# Adafruit_VCNL4200_Long_Distance_IR_Senso.net
KiCad netlist of a schematic drawn in EAGLE
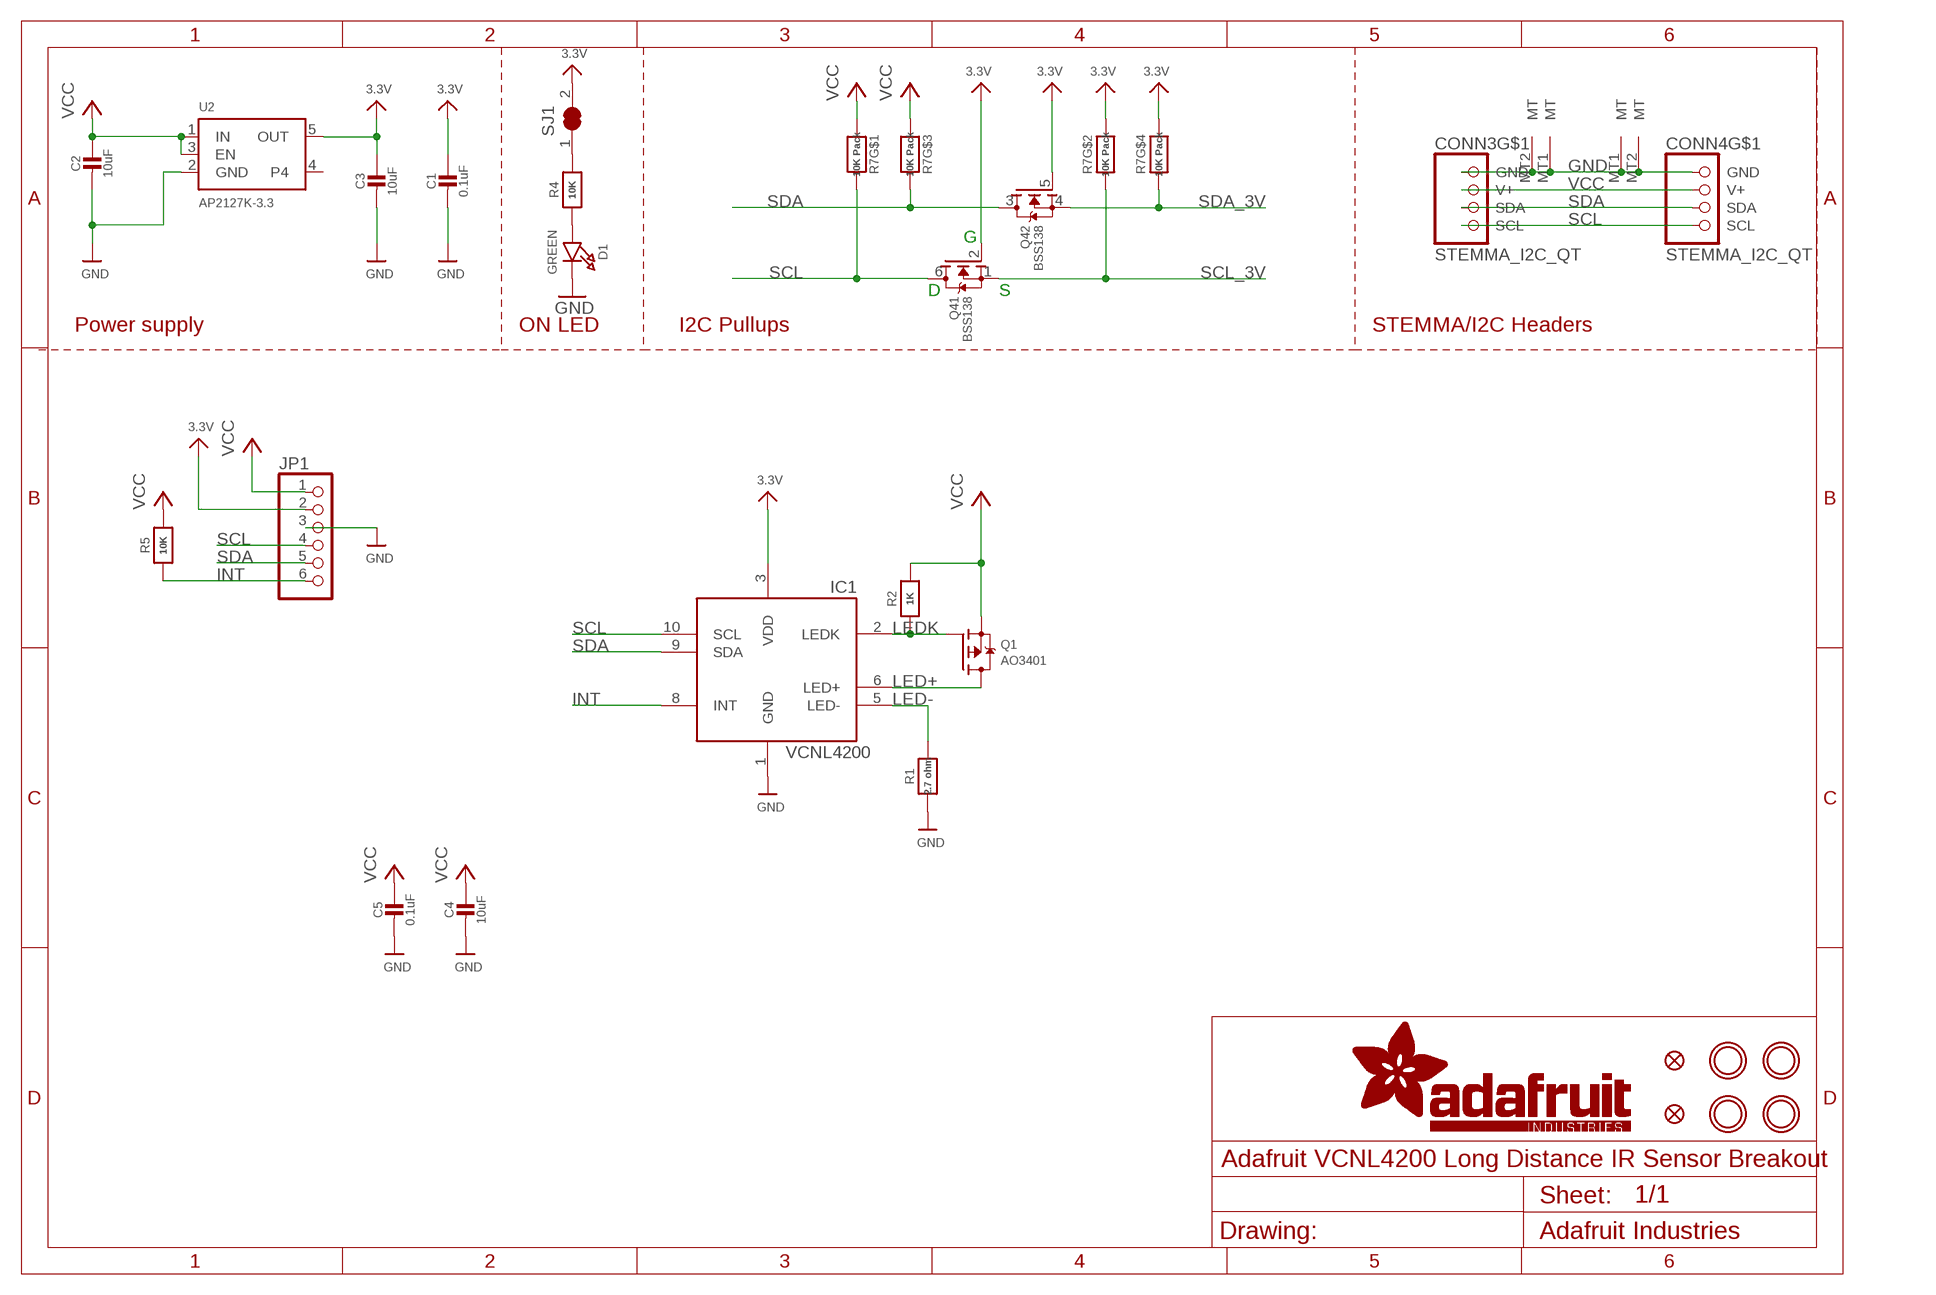
[diagram p0: schematic, sheet 1]

(export (version "E")
  (design (tool "Eeschema 10.0.6"))
  (components
    (comp (ref "C1")
      (value "0.1uF")
      (footprint "eagle-import:0603-NO")
      (libsource (lib "eagle-import") (part "CAP_CERAMIC0603_NO"))
    )
    (comp (ref "C2")
      (value "10uF")
      (footprint "eagle-import:0805-NO")
      (libsource (lib "eagle-import") (part "CAP_CERAMIC0805-NOOUTLINE"))
    )
    (comp (ref "C3")
      (value "10uF")
      (footprint "eagle-import:0805-NO")
      (libsource (lib "eagle-import") (part "CAP_CERAMIC0805-NOOUTLINE"))
    )
    (comp (ref "C4")
      (value "10uF")
      (footprint "eagle-import:0805-NO")
      (libsource (lib "eagle-import") (part "CAP_CERAMIC0805-NOOUTLINE"))
    )
    (comp (ref "C5")
      (value "0.1uF")
      (footprint "eagle-import:0603-NO")
      (libsource (lib "eagle-import") (part "CAP_CERAMIC0603_NO"))
    )
    (comp (ref "CONN3")
      (value "STEMMA_I2C_QT")
      (footprint "eagle-import:JST_SH4")
      (libsource (lib "eagle-import") (part "STEMMA_I2C_QT"))
    )
    (comp (ref "CONN4")
      (value "STEMMA_I2C_QT")
      (footprint "eagle-import:JST_SH4")
      (libsource (lib "eagle-import") (part "STEMMA_I2C_QT"))
    )
    (comp (ref "D1")
      (value "GREEN")
      (footprint "eagle-import:CHIPLED_0603_NOOUTLINE")
      (libsource (lib "eagle-import") (part "LED0603_NOOUTLINE"))
    )
    (comp (ref "FID3")
      (value "FIDUCIAL_1MM")
      (footprint "eagle-import:FIDUCIAL_1MM")
      (libsource (lib "eagle-import") (part "FIDUCIAL_1MM"))
    )
    (comp (ref "FID4")
      (value "FIDUCIAL_1MM")
      (footprint "eagle-import:FIDUCIAL_1MM")
      (libsource (lib "eagle-import") (part "FIDUCIAL_1MM"))
    )
    (comp (ref "IC1")
      (value "VCNL4200")
      (footprint "eagle-import:VCNL4200")
      (libsource (lib "eagle-import") (part "VCNL4200"))
    )
    (comp (ref "JP1")
      (value "HEADER-1X670MIL")
      (footprint "eagle-import:1X06_ROUND_70")
      (libsource (lib "eagle-import") (part "HEADER-1X670MIL"))
    )
    (comp (ref "Q1")
      (value "AO3401")
      (footprint "eagle-import:SOT23-WIDE")
      (libsource (lib "eagle-import") (part "MOSFET-PWIDE"))
    )
    (comp (ref "Q4")
      (value "BSS138")
      (footprint "eagle-import:SOT363")
      (libsource (lib "eagle-import") (part "MOSFET-N_DUAL"))
    )
    (comp (ref "R1")
      (value "2.7 ohm")
      (footprint "eagle-import:0603-NO")
      (libsource (lib "eagle-import") (part "RESISTOR_0603_NOOUT"))
    )
    (comp (ref "R2")
      (value "1K")
      (footprint "eagle-import:0603-NO")
      (libsource (lib "eagle-import") (part "RESISTOR_0603_NOOUT"))
    )
    (comp (ref "R4")
      (value "10K")
      (footprint "eagle-import:0603-NO")
      (libsource (lib "eagle-import") (part "RESISTOR_0603_NOOUT"))
    )
    (comp (ref "R5")
      (value "10K")
      (footprint "eagle-import:0603-NO")
      (libsource (lib "eagle-import") (part "RESISTOR_0603_NOOUT"))
    )
    (comp (ref "R7")
      (value "10K Pack")
      (footprint "eagle-import:RESPACK_4X0603")
      (libsource (lib "eagle-import") (part "RESISTOR_4PACK"))
    )
    (comp (ref "SJ1")
      (value "SOLDERJUMPER_CLOSED")
      (footprint "eagle-import:SOLDERJUMPER_CLOSEDWIRE")
      (libsource (lib "eagle-import") (part "SOLDERJUMPER_CLOSED"))
    )
    (comp (ref "U$1")
      (value "MOUNTINGHOLE2.5")
      (footprint "eagle-import:MOUNTINGHOLE_2.5_PLATED")
      (libsource (lib "eagle-import") (part "MOUNTINGHOLE2.5"))
    )
    (comp (ref "U$17")
      (value "MOUNTINGHOLE2.5")
      (footprint "eagle-import:MOUNTINGHOLE_2.5_PLATED")
      (libsource (lib "eagle-import") (part "MOUNTINGHOLE2.5"))
    )
    (comp (ref "U$19")
      (value "MOUNTINGHOLE2.5")
      (footprint "eagle-import:MOUNTINGHOLE_2.5_PLATED")
      (libsource (lib "eagle-import") (part "MOUNTINGHOLE2.5"))
    )
    (comp (ref "U$21")
      (value "MOUNTINGHOLE2.5")
      (footprint "eagle-import:MOUNTINGHOLE_2.5_PLATED")
      (libsource (lib "eagle-import") (part "MOUNTINGHOLE2.5"))
    )
    (comp (ref "U2")
      (value "AP2127K-3.3")
      (footprint "eagle-import:SOT23-5")
      (libsource (lib "eagle-import") (part "VREG_SOT23-5"))
    )
  )
  (nets
    (net (code "1") (name "/INT") (class "Default")
      (node (ref "IC1") (pin "8") (pinfunction "INT_8") (pintype "output"))
      (node (ref "JP1") (pin "6") (pinfunction "6_6") (pintype "passive"))
      (node (ref "R5") (pin "1") (pinfunction "1_1") (pintype "passive"))
    )
    (net (code "2") (name "/LED+") (class "Default")
      (node (ref "IC1") (pin "6") (pinfunction "LED+_6") (pintype "input"))
      (node (ref "Q1") (pin "3") (pinfunction "D_3") (pintype "passive"))
    )
    (net (code "3") (name "/LED-") (class "Default")
      (node (ref "IC1") (pin "5") (pinfunction "LED-_5") (pintype "input"))
      (node (ref "R1") (pin "2") (pinfunction "2_2") (pintype "passive"))
    )
    (net (code "4") (name "/LEDK") (class "Default")
      (node (ref "IC1") (pin "2") (pinfunction "LEDK_2") (pintype "input"))
      (node (ref "Q1") (pin "1") (pinfunction "G_1") (pintype "passive"))
      (node (ref "R2") (pin "1") (pinfunction "1_1") (pintype "passive"))
    )
    (net (code "5") (name "/SCL") (class "Default")
      (node (ref "CONN3") (pin "4") (pinfunction "SCL_4") (pintype "passive"))
      (node (ref "CONN4") (pin "4") (pinfunction "SCL_4") (pintype "passive"))
      (node (ref "IC1") (pin "10") (pinfunction "SCL_10") (pintype "bidirectional"))
      (node (ref "JP1") (pin "4") (pinfunction "4_4") (pintype "passive"))
      (node (ref "Q4") (pin "6") (pinfunction "D_6") (pintype "bidirectional"))
      (node (ref "R7") (pin "8") (pinfunction "2_8") (pintype "passive"))
    )
    (net (code "6") (name "/SCL_3V") (class "Default")
      (node (ref "Q4") (pin "1") (pinfunction "S_1") (pintype "bidirectional"))
      (node (ref "R7") (pin "7") (pinfunction "2_7") (pintype "passive"))
    )
    (net (code "7") (name "/SDA") (class "Default")
      (node (ref "CONN3") (pin "3") (pinfunction "SDA_3") (pintype "passive"))
      (node (ref "CONN4") (pin "3") (pinfunction "SDA_3") (pintype "passive"))
      (node (ref "IC1") (pin "9") (pinfunction "SDA_9") (pintype "bidirectional"))
      (node (ref "JP1") (pin "5") (pinfunction "5_5") (pintype "passive"))
      (node (ref "Q4") (pin "3") (pinfunction "D_3") (pintype "bidirectional"))
      (node (ref "R7") (pin "6") (pinfunction "2_6") (pintype "passive"))
    )
    (net (code "8") (name "/SDA_3V") (class "Default")
      (node (ref "Q4") (pin "4") (pinfunction "S_4") (pintype "bidirectional"))
      (node (ref "R7") (pin "5") (pinfunction "2_5") (pintype "passive"))
    )
    (net (code "9") (name "3.3V") (class "Default")
      (node (ref "C1") (pin "1") (pinfunction "1_1") (pintype "passive"))
      (node (ref "C3") (pin "1") (pinfunction "1_1") (pintype "passive"))
      (node (ref "IC1") (pin "3") (pinfunction "VDD_3") (pintype "power_in"))
      (node (ref "JP1") (pin "2") (pinfunction "2_2") (pintype "passive"))
      (node (ref "Q4") (pin "2") (pinfunction "G_2") (pintype "bidirectional"))
      (node (ref "Q4") (pin "5") (pinfunction "G_5") (pintype "bidirectional"))
      (node (ref "R7") (pin "2") (pinfunction "1_2") (pintype "passive"))
      (node (ref "R7") (pin "4") (pinfunction "1_4") (pintype "passive"))
      (node (ref "SJ1") (pin "2") (pinfunction "2_2") (pintype "passive"))
      (node (ref "U2") (pin "5") (pinfunction "OUT_5") (pintype "power_in"))
    )
    (net (code "10") (name "GND") (class "Default")
      (node (ref "C1") (pin "2") (pinfunction "2_2") (pintype "passive"))
      (node (ref "C2") (pin "2") (pinfunction "2_2") (pintype "passive"))
      (node (ref "C3") (pin "2") (pinfunction "2_2") (pintype "passive"))
      (node (ref "C4") (pin "2") (pinfunction "2_2") (pintype "passive"))
      (node (ref "C5") (pin "2") (pinfunction "2_2") (pintype "passive"))
      (node (ref "CONN3") (pin "1") (pinfunction "GND_1") (pintype "passive"))
      (node (ref "CONN3") (pin "MT1") (pinfunction "MT_MT1") (pintype "bidirectional"))
      (node (ref "CONN3") (pin "MT2") (pinfunction "MT_MT2") (pintype "bidirectional"))
      (node (ref "CONN4") (pin "1") (pinfunction "GND_1") (pintype "passive"))
      (node (ref "CONN4") (pin "MT1") (pinfunction "MT_MT1") (pintype "bidirectional"))
      (node (ref "CONN4") (pin "MT2") (pinfunction "MT_MT2") (pintype "bidirectional"))
      (node (ref "D1") (pin "C") (pinfunction "C_C") (pintype "passive"))
      (node (ref "IC1") (pin "1") (pinfunction "GND_1") (pintype "power_in"))
      (node (ref "JP1") (pin "3") (pinfunction "3_3") (pintype "passive"))
      (node (ref "R1") (pin "1") (pinfunction "1_1") (pintype "passive"))
      (node (ref "U2") (pin "2") (pinfunction "GND_2") (pintype "power_in"))
    )
    (net (code "11") (name "Net-(D1-PadA)") (class "Default")
      (node (ref "D1") (pin "A") (pinfunction "A_A") (pintype "passive"))
      (node (ref "R4") (pin "1") (pinfunction "1_1") (pintype "passive"))
    )
    (net (code "12") (name "Net-(R4-Pad2)") (class "Default")
      (node (ref "R4") (pin "2") (pinfunction "2_2") (pintype "passive"))
      (node (ref "SJ1") (pin "1") (pinfunction "1_1") (pintype "passive"))
    )
    (net (code "13") (name "VCC") (class "Default")
      (node (ref "C2") (pin "1") (pinfunction "1_1") (pintype "passive"))
      (node (ref "C4") (pin "1") (pinfunction "1_1") (pintype "passive"))
      (node (ref "C5") (pin "1") (pinfunction "1_1") (pintype "passive"))
      (node (ref "CONN3") (pin "2") (pinfunction "V+_2") (pintype "passive"))
      (node (ref "CONN4") (pin "2") (pinfunction "V+_2") (pintype "passive"))
      (node (ref "JP1") (pin "1") (pinfunction "1_1") (pintype "passive"))
      (node (ref "Q1") (pin "2") (pinfunction "S_2") (pintype "passive"))
      (node (ref "R2") (pin "2") (pinfunction "2_2") (pintype "passive"))
      (node (ref "R5") (pin "2") (pinfunction "2_2") (pintype "passive"))
      (node (ref "R7") (pin "1") (pinfunction "1_1") (pintype "passive"))
      (node (ref "R7") (pin "3") (pinfunction "1_3") (pintype "passive"))
      (node (ref "U2") (pin "1") (pinfunction "IN_1") (pintype "power_in"))
      (node (ref "U2") (pin "3") (pinfunction "EN_3") (pintype "input"))
    )
    (net (code "14") (name "unconnected-(U2-P4-Pad4)") (class "Default")
      (node (ref "U2") (pin "4") (pinfunction "P4_4") (pintype "bidirectional"))
    )
  )
)
